# Geeky__Sheet1_copy_2023-02-18.net
KiCad netlist of a schematic drawn in Altium Designer
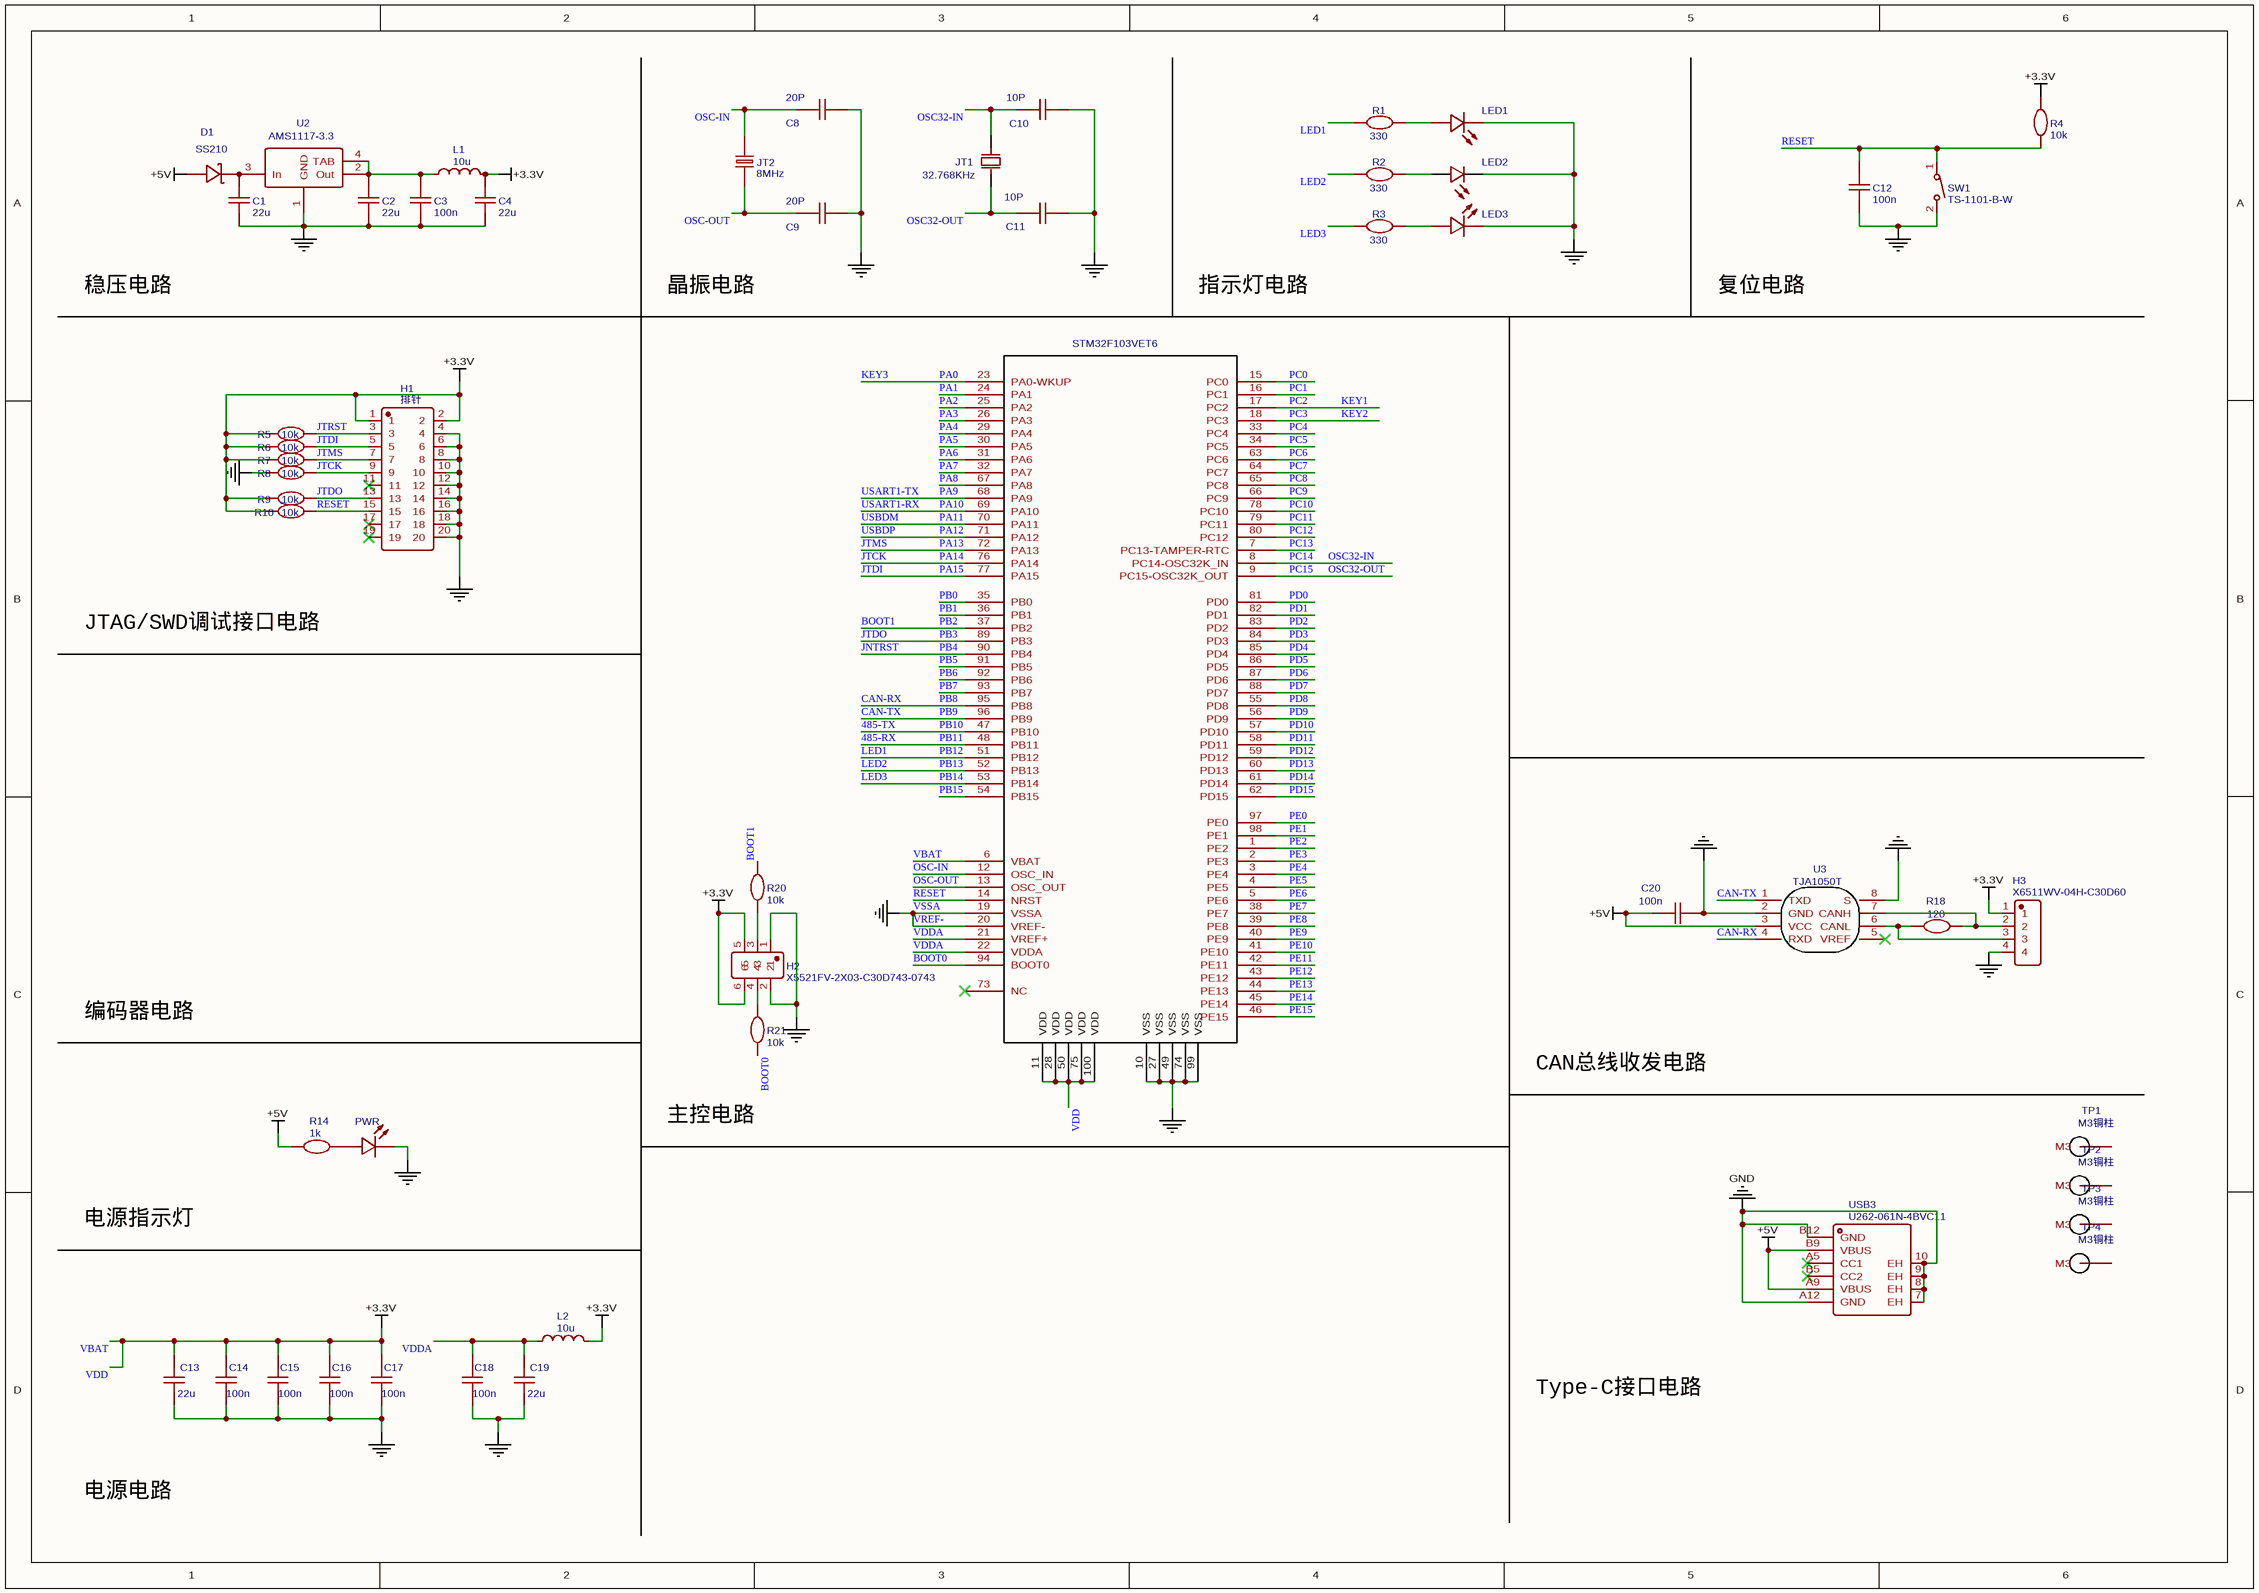
[diagram p0: _Geeky_ Sheet1 copy_2023-02-18.schdoc]

(export (version "E")
  (design (tool "Eeschema 10.0.6"))
  (components
    (comp (ref "C1") (value "22u") (footprint "0805") (libsource (lib "altium-import") (part "root_2_22u_")))
    (comp (ref "C2") (value "22u") (footprint "0805") (libsource (lib "altium-import") (part "root_2_22u_")))
    (comp (ref "C3")
      (value "100n")
      (footprint "0805")
      (libsource (lib "altium-import") (part "root_2_100n_"))
    )
    (comp (ref "C4") (value "22u") (footprint "0805") (libsource (lib "altium-import") (part "root_2_22u_")))
    (comp (ref "C8") (value "20P") (footprint "0805") (libsource (lib "altium-import") (part "root_1_20P_")))
    (comp (ref "C9") (value "20P") (footprint "0805") (libsource (lib "altium-import") (part "root_1_20P_")))
    (comp (ref "C10") (value "10P") (footprint "0805") (libsource (lib "altium-import") (part "root_1_10P_")))
    (comp (ref "C11") (value "10P") (footprint "0805") (libsource (lib "altium-import") (part "root_1_10P_")))
    (comp (ref "C12")
      (value "100n")
      (footprint "0805")
      (libsource (lib "altium-import") (part "root_2_100n_"))
    )
    (comp (ref "C13") (value "22u") (footprint "0805") (libsource (lib "altium-import") (part "root_0_22u_")))
    (comp (ref "C14")
      (value "100n")
      (footprint "0805")
      (libsource (lib "altium-import") (part "root_0_100n_"))
    )
    (comp (ref "C15")
      (value "100n")
      (footprint "0805")
      (libsource (lib "altium-import") (part "root_0_100n_"))
    )
    (comp (ref "C16")
      (value "100n")
      (footprint "0805")
      (libsource (lib "altium-import") (part "root_0_100n_"))
    )
    (comp (ref "C17")
      (value "100n")
      (footprint "0805")
      (libsource (lib "altium-import") (part "root_0_100n_"))
    )
    (comp (ref "C18")
      (value "100n")
      (footprint "0805")
      (libsource (lib "altium-import") (part "root_0_100n_"))
    )
    (comp (ref "C19") (value "22u") (footprint "0805") (libsource (lib "altium-import") (part "root_0_22u_")))
    (comp (ref "C20")
      (value "100n")
      (footprint "0805")
      (libsource (lib "altium-import") (part "root_3_100n_"))
    )
    (comp (ref "D1")
      (value "SS210")
      (footprint "SMA_L4.3-W2.6-LS5.2-FD")
      (fields (field (name "BOM_SUPPLIER PART") "C14996"))
      (libsource (lib "altium-import") (part "root_0_SS210_"))
    )
    (comp (ref "H1")
      (value "排针")
      (footprint "HDR-TH_20P-P2.54-V-M-R2-C10-S2.54-3")
      (fields
        (field (name "BOM_SUPPLIER PART") "C2764589")
        (field (name "BOM_MANUFACTURER PART") "X5521WV-2X10-C46D46-1220")
        (field (name "CONTRIBUTOR") "LCSC")
      )
      (libsource (lib "altium-import") (part "root_0_X5521WV-2X10-C46D46-1220_"))
    )
    (comp (ref "H2")
      (value "X5521FV-2X03-C30D743-0743")
      (footprint "HDR-TH_6P-P2.54-V-F-R2-C3-S2.54-3")
      (fields (field (name "BOM_SUPPLIER PART") "C2764576") (field (name "CONTRIBUTOR") "LCSC"))
      (libsource (lib "altium-import") (part "root_3_X5521FV-2X03-C30D743-0743_"))
    )
    (comp (ref "H3")
      (value "X6511WV-04H-C30D60")
      (footprint "HDR-TH_4P-P2.54-V-M")
      (fields (field (name "BOM_SUPPLIER PART") "C706876") (field (name "CONTRIBUTOR") "LCSC"))
      (libsource (lib "altium-import") (part "root_0_X6511WV-04H-C30D60_"))
    )
    (comp (ref "JT1")
      (value "32.768KHz")
      (footprint "OSC-SMD_L3.2-W1.5")
      (fields
        (field (name "BOM_MANUFACTURER PART") "NX3215SA 32.768KHZ 12.5PF 20PPM")
        (field (name "BOM_SUPPLIER PART") "C70509")
      )
      (libsource (lib "altium-import") (part "root_1_32.768KHz_"))
    )
    (comp (ref "JT2")
      (value "8MHz")
      (footprint "HC-49US_L11.5-W4.5-P4.88")
      (fields
        (field (name "BOM_SUPPLIER PART") "C295085")
        (field (name "BOM_MANUFACTURER PART") "XIHCELNANF-48MHZ")
        (field (name "CONTRIBUTOR") "LCSC")
      )
      (libsource (lib "altium-import") (part "root_1_8MHz_"))
    )
    (comp (ref "L1") (value "10u") (footprint "0805") (libsource (lib "altium-import") (part "root_0_10u_")))
    (comp (ref "L2") (value "10u") (footprint "0805") (libsource (lib "altium-import") (part "root_0_10u_")))
    (comp (ref "LED1")
      (value "17-21SUYC/TR8")
      (footprint "LED0805-RD")
      (fields (field (name "BOM_SUPPLIER PART") "C2296"))
      (libsource (lib "altium-import") (part "root_2_17-21SUYC/TR8_"))
    )
    (comp (ref "LED2")
      (value "17-21/BHC-XL2M2TY/3T")
      (footprint "LED0805-RD")
      (fields (field (name "BOM_SUPPLIER PART") "C72035"))
      (libsource (lib "altium-import") (part "root_2_17-21/BHC-XL2M2TY/3T_"))
    )
    (comp (ref "LED3")
      (value "D-W080508W1-KS2")
      (footprint "LED-0805")
      (fields (field (name "BOM_SUPPLIER PART") "C130115") (field (name "CONTRIBUTOR") "LCSC"))
      (libsource (lib "altium-import") (part "root_0_D-W080508W1-KS2_"))
    )
    (comp (ref "PWR")
      (value "17-21SURC/S530-A2/TR8")
      (footprint "LED-0805")
      (fields (field (name "BOM_SUPPLIER PART") "C131244") (field (name "CONTRIBUTOR") "LCSC"))
      (libsource (lib "altium-import") (part "root_0_17-21SURC/S530-A2/TR8_"))
    )
    (comp (ref "R1") (value "330") (footprint "0805") (libsource (lib "altium-import") (part "root_0_330_")))
    (comp (ref "R2") (value "330") (footprint "0805") (libsource (lib "altium-import") (part "root_0_330_")))
    (comp (ref "R3") (value "330") (footprint "0805") (libsource (lib "altium-import") (part "root_0_330_")))
    (comp (ref "R4") (value "10k") (footprint "0805") (libsource (lib "altium-import") (part "root_1_10k_")))
    (comp (ref "R5") (value "10k") (footprint "0805") (libsource (lib "altium-import") (part "root_2_10k_")))
    (comp (ref "R6") (value "10k") (footprint "0805") (libsource (lib "altium-import") (part "root_2_10k_")))
    (comp (ref "R7") (value "10k") (footprint "0805") (libsource (lib "altium-import") (part "root_2_10k_")))
    (comp (ref "R8") (value "10k") (footprint "0805") (libsource (lib "altium-import") (part "root_2_10k_")))
    (comp (ref "R9") (value "10k") (footprint "0805") (libsource (lib "altium-import") (part "root_2_10k_")))
    (comp (ref "R10") (value "10k") (footprint "0805") (libsource (lib "altium-import") (part "root_2_10k_")))
    (comp (ref "R14") (value "1k") (footprint "0805") (libsource (lib "altium-import") (part "root_0_1k_")))
    (comp (ref "R18") (value "120") (footprint "0805") (libsource (lib "altium-import") (part "root_0_120_")))
    (comp (ref "R20") (value "10k") (footprint "0805") (libsource (lib "altium-import") (part "root_1_10k_")))
    (comp (ref "R21") (value "10k") (footprint "0805") (libsource (lib "altium-import") (part "root_1_10k_")))
    (comp (ref "SW1")
      (value "TS-1101-B-W")
      (footprint "KEY-SMD_2P-L6.0-W3.6-P7.4-LS8.0-L")
      (fields (field (name "BOM_SUPPLIER PART") "C500065") (field (name "CONTRIBUTOR") "LCSC"))
      (libsource (lib "altium-import") (part "root_3_TS-1101-B-W_"))
    )
    (comp (ref "TP1")
      (value "M3铜柱")
      (footprint "M3铜柱_LCEDA")
      (fields (field (name "CONTRIBUTOR") "LGW123456"))
      (libsource (lib "altium-import") (part "root_0_M3铜柱_"))
    )
    (comp (ref "TP2")
      (value "M3铜柱")
      (footprint "M3铜柱_LCEDA")
      (fields (field (name "CONTRIBUTOR") "LGW123456"))
      (libsource (lib "altium-import") (part "root_0_M3铜柱_"))
    )
    (comp (ref "TP3")
      (value "M3铜柱")
      (footprint "M3铜柱_LCEDA")
      (fields (field (name "CONTRIBUTOR") "LGW123456"))
      (libsource (lib "altium-import") (part "root_0_M3铜柱_"))
    )
    (comp (ref "TP4")
      (value "M3铜柱")
      (footprint "M3铜柱_LCEDA")
      (fields (field (name "CONTRIBUTOR") "LGW123456"))
      (libsource (lib "altium-import") (part "root_0_M3铜柱_"))
    )
    (comp (ref "U1")
      (value "STM32F103VET6")
      (footprint "LQFP-100_L14.0-W14.0-P0.50-LS16.0-BL")
      (fields (field (name "BOM_SUPPLIER PART") "C8308"))
      (libsource (lib "altium-import") (part "root_0_STM32F103VET6_"))
    )
    (comp (ref "U2")
      (value "AMS1117-3.3")
      (footprint "SOT-223_L6.5-W3.5-P2.30-LS7.0-BR")
      (fields (field (name "BOM_SUPPLIER PART") "C165482") (field (name "CONTRIBUTOR") "LCSC"))
      (libsource (lib "altium-import") (part "root_0_AMS1117-3.3_"))
    )
    (comp (ref "U3")
      (value "TJA1050T")
      (footprint "SOIC-8_L5.0-W4.0-P1.27-LS6.0-BL")
      (fields
        (field (name "BOM_MANUFACTURER PART") "TJA1050T/CM,118")
        (field (name "BOM_SUPPLIER PART") "C6952")
      )
      (libsource (lib "altium-import") (part "root_0_TJA1050T_"))
    )
    (comp (ref "USB3")
      (value "U262-061N-4BVC11")
      (footprint "USB-SMD_U262-061N-4BVC11")
      (fields (field (name "BOM_SUPPLIER PART") "C2764612") (field (name "CONTRIBUTOR") "LCSC"))
      (libsource (lib "altium-import") (part "root_0_U262-061N-4BVC11_"))
    )
  )
  (nets
    (net (code "1") (name "+3.3V") (class "Default")
      (node (ref "C13") (pin "2") (pinfunction "2_2") (pintype "passive"))
      (node (ref "C14") (pin "2") (pinfunction "2_2") (pintype "passive"))
      (node (ref "C15") (pin "2") (pinfunction "2_2") (pintype "passive"))
      (node (ref "C16") (pin "2") (pinfunction "2_2") (pintype "passive"))
      (node (ref "C17") (pin "2") (pinfunction "2_2") (pintype "passive"))
      (node (ref "C4") (pin "1") (pinfunction "1_1") (pintype "passive"))
      (node (ref "H1") (pin "1") (pinfunction "1_1") (pintype "passive"))
      (node (ref "H1") (pin "2") (pinfunction "2_2") (pintype "passive"))
      (node (ref "H2") (pin "5") (pinfunction "5_5") (pintype "passive"))
      (node (ref "H2") (pin "6") (pinfunction "6_6") (pintype "passive"))
      (node (ref "H3") (pin "1") (pinfunction "1_1") (pintype "passive"))
      (node (ref "L1") (pin "2") (pinfunction "2_2") (pintype "passive"))
      (node (ref "L2") (pin "2") (pinfunction "2_2") (pintype "passive"))
      (node (ref "R10") (pin "2") (pinfunction "2_2") (pintype "passive"))
      (node (ref "R4") (pin "2") (pinfunction "2_2") (pintype "passive"))
      (node (ref "R5") (pin "2") (pinfunction "2_2") (pintype "passive"))
      (node (ref "R6") (pin "2") (pinfunction "2_2") (pintype "passive"))
      (node (ref "R7") (pin "2") (pinfunction "2_2") (pintype "passive"))
      (node (ref "R9") (pin "2") (pinfunction "2_2") (pintype "passive"))
      (node (ref "U1") (pin "100") (pinfunction "VDD_100") (pintype "passive"))
      (node (ref "U1") (pin "11") (pinfunction "VDD_11") (pintype "passive"))
      (node (ref "U1") (pin "28") (pinfunction "VDD_28") (pintype "passive"))
      (node (ref "U1") (pin "50") (pinfunction "VDD_50") (pintype "passive"))
      (node (ref "U1") (pin "6") (pinfunction "VBAT_6") (pintype "passive"))
      (node (ref "U1") (pin "75") (pinfunction "VDD_75") (pintype "passive"))
    )
    (net (code "2") (name "+5V") (class "Default")
      (node (ref "C20") (pin "1") (pinfunction "1_1") (pintype "passive"))
      (node (ref "D1") (pin "1") (pinfunction "A_1") (pintype "passive"))
      (node (ref "R14") (pin "1") (pinfunction "1_1") (pintype "passive"))
      (node (ref "U3") (pin "3") (pinfunction "VCC_3") (pintype "passive"))
      (node (ref "USB3") (pin "A9") (pinfunction "VBUS_A9") (pintype "passive"))
      (node (ref "USB3") (pin "B9") (pinfunction "VBUS_B9") (pintype "passive"))
    )
    (net (code "3") (name "/485-RX") (class "Default")
      (node (ref "U1") (pin "48") (pinfunction "PB11_48") (pintype "passive"))
    )
    (net (code "4") (name "/485-TX") (class "Default")
      (node (ref "U1") (pin "47") (pinfunction "PB10_47") (pintype "passive"))
    )
    (net (code "5") (name "/BOOT0") (class "Default")
      (node (ref "R21") (pin "1") (pinfunction "1_1") (pintype "passive"))
      (node (ref "U1") (pin "94") (pinfunction "BOOT0_94") (pintype "passive"))
    )
    (net (code "6") (name "/BOOT1") (class "Default")
      (node (ref "R20") (pin "2") (pinfunction "2_2") (pintype "passive"))
      (node (ref "U1") (pin "37") (pinfunction "PB2_37") (pintype "passive"))
    )
    (net (code "7") (name "/CAN-RX") (class "Default")
      (node (ref "U1") (pin "95") (pinfunction "PB8_95") (pintype "passive"))
      (node (ref "U3") (pin "4") (pinfunction "RXD_4") (pintype "passive"))
    )
    (net (code "8") (name "/CAN-TX") (class "Default")
      (node (ref "U1") (pin "96") (pinfunction "PB9_96") (pintype "passive"))
      (node (ref "U3") (pin "1") (pinfunction "TXD_1") (pintype "passive"))
    )
    (net (code "9") (name "/JNTRST") (class "Default")
      (node (ref "U1") (pin "90") (pinfunction "PB4_90") (pintype "passive"))
    )
    (net (code "10") (name "/JTCK") (class "Default")
      (node (ref "H1") (pin "9") (pinfunction "9_9") (pintype "passive"))
      (node (ref "R8") (pin "1") (pinfunction "1_1") (pintype "passive"))
      (node (ref "U1") (pin "76") (pinfunction "PA14_76") (pintype "passive"))
    )
    (net (code "11") (name "/JTDI") (class "Default")
      (node (ref "H1") (pin "5") (pinfunction "5_5") (pintype "passive"))
      (node (ref "R6") (pin "1") (pinfunction "1_1") (pintype "passive"))
      (node (ref "U1") (pin "77") (pinfunction "PA15_77") (pintype "passive"))
    )
    (net (code "12") (name "/JTDO") (class "Default")
      (node (ref "H1") (pin "13") (pinfunction "13_13") (pintype "passive"))
      (node (ref "R9") (pin "1") (pinfunction "1_1") (pintype "passive"))
      (node (ref "U1") (pin "89") (pinfunction "PB3_89") (pintype "passive"))
    )
    (net (code "13") (name "/JTMS") (class "Default")
      (node (ref "H1") (pin "7") (pinfunction "7_7") (pintype "passive"))
      (node (ref "R7") (pin "1") (pinfunction "1_1") (pintype "passive"))
      (node (ref "U1") (pin "72") (pinfunction "PA13_72") (pintype "passive"))
    )
    (net (code "14") (name "/JTRST") (class "Default")
      (node (ref "H1") (pin "3") (pinfunction "3_3") (pintype "passive"))
      (node (ref "R5") (pin "1") (pinfunction "1_1") (pintype "passive"))
    )
    (net (code "15") (name "/KEY1") (class "Default")
      (node (ref "U1") (pin "17") (pinfunction "PC2_17") (pintype "passive"))
    )
    (net (code "16") (name "/KEY2") (class "Default")
      (node (ref "U1") (pin "18") (pinfunction "PC3_18") (pintype "passive"))
    )
    (net (code "17") (name "/KEY3") (class "Default")
      (node (ref "U1") (pin "23") (pinfunction "PA0-WKUP_23") (pintype "passive"))
    )
    (net (code "18") (name "/LED1") (class "Default")
      (node (ref "R1") (pin "1") (pinfunction "1_1") (pintype "passive"))
      (node (ref "U1") (pin "51") (pinfunction "PB12_51") (pintype "passive"))
    )
    (net (code "19") (name "/LED2") (class "Default")
      (node (ref "R2") (pin "1") (pinfunction "1_1") (pintype "passive"))
      (node (ref "U1") (pin "52") (pinfunction "PB13_52") (pintype "passive"))
    )
    (net (code "20") (name "/LED3") (class "Default")
      (node (ref "R3") (pin "1") (pinfunction "1_1") (pintype "passive"))
      (node (ref "U1") (pin "53") (pinfunction "PB14_53") (pintype "passive"))
    )
    (net (code "21") (name "/OSC-IN") (class "Default")
      (node (ref "C8") (pin "2") (pinfunction "2_2") (pintype "passive"))
      (node (ref "JT2") (pin "2") (pinfunction "2_2") (pintype "passive"))
      (node (ref "U1") (pin "12") (pinfunction "OSC_IN_12") (pintype "passive"))
    )
    (net (code "22") (name "/OSC-OUT") (class "Default")
      (node (ref "C9") (pin "2") (pinfunction "2_2") (pintype "passive"))
      (node (ref "JT2") (pin "1") (pinfunction "1_1") (pintype "passive"))
      (node (ref "U1") (pin "13") (pinfunction "OSC_OUT_13") (pintype "passive"))
    )
    (net (code "23") (name "/OSC32-IN") (class "Default")
      (node (ref "C10") (pin "2") (pinfunction "2_2") (pintype "passive"))
      (node (ref "JT1") (pin "2") (pinfunction "OSC2_2") (pintype "passive"))
      (node (ref "U1") (pin "8") (pinfunction "PC14-OSC32K_IN_8") (pintype "passive"))
    )
    (net (code "24") (name "/OSC32-OUT") (class "Default")
      (node (ref "C11") (pin "2") (pinfunction "2_2") (pintype "passive"))
      (node (ref "JT1") (pin "1") (pinfunction "OSC1_1") (pintype "passive"))
      (node (ref "U1") (pin "9") (pinfunction "PC15-OSC32K_OUT_9") (pintype "passive"))
    )
    (net (code "25") (name "/PA1") (class "Default")
      (node (ref "U1") (pin "24") (pinfunction "PA1_24") (pintype "passive"))
    )
    (net (code "26") (name "/PA2") (class "Default")
      (node (ref "U1") (pin "25") (pinfunction "PA2_25") (pintype "passive"))
    )
    (net (code "27") (name "/PA3") (class "Default")
      (node (ref "U1") (pin "26") (pinfunction "PA3_26") (pintype "passive"))
    )
    (net (code "28") (name "/PA4") (class "Default")
      (node (ref "U1") (pin "29") (pinfunction "PA4_29") (pintype "passive"))
    )
    (net (code "29") (name "/PA5") (class "Default")
      (node (ref "U1") (pin "30") (pinfunction "PA5_30") (pintype "passive"))
    )
    (net (code "30") (name "/PA6") (class "Default")
      (node (ref "U1") (pin "31") (pinfunction "PA6_31") (pintype "passive"))
    )
    (net (code "31") (name "/PA7") (class "Default")
      (node (ref "U1") (pin "32") (pinfunction "PA7_32") (pintype "passive"))
    )
    (net (code "32") (name "/PA8") (class "Default")
      (node (ref "U1") (pin "67") (pinfunction "PA8_67") (pintype "passive"))
    )
    (net (code "33") (name "/PA9") (class "Default")
      (node (ref "U1") (pin "68") (pinfunction "PA9_68") (pintype "passive"))
    )
    (net (code "34") (name "/PA10") (class "Default")
      (node (ref "U1") (pin "69") (pinfunction "PA10_69") (pintype "passive"))
    )
    (net (code "35") (name "/PA11") (class "Default")
      (node (ref "U1") (pin "70") (pinfunction "PA11_70") (pintype "passive"))
    )
    (net (code "36") (name "/PA12") (class "Default")
      (node (ref "U1") (pin "71") (pinfunction "PA12_71") (pintype "passive"))
    )
    (net (code "37") (name "/PB0") (class "Default")
      (node (ref "U1") (pin "35") (pinfunction "PB0_35") (pintype "passive"))
    )
    (net (code "38") (name "/PB1") (class "Default")
      (node (ref "U1") (pin "36") (pinfunction "PB1_36") (pintype "passive"))
    )
    (net (code "39") (name "/PB5") (class "Default")
      (node (ref "U1") (pin "91") (pinfunction "PB5_91") (pintype "passive"))
    )
    (net (code "40") (name "/PB6") (class "Default")
      (node (ref "U1") (pin "92") (pinfunction "PB6_92") (pintype "passive"))
    )
    (net (code "41") (name "/PB7") (class "Default")
      (node (ref "U1") (pin "93") (pinfunction "PB7_93") (pintype "passive"))
    )
    (net (code "42") (name "/PB15") (class "Default")
      (node (ref "U1") (pin "54") (pinfunction "PB15_54") (pintype "passive"))
    )
    (net (code "43") (name "/PC0") (class "Default")
      (node (ref "U1") (pin "15") (pinfunction "PC0_15") (pintype "passive"))
    )
    (net (code "44") (name "/PC1") (class "Default")
      (node (ref "U1") (pin "16") (pinfunction "PC1_16") (pintype "passive"))
    )
    (net (code "45") (name "/PC4") (class "Default")
      (node (ref "U1") (pin "33") (pinfunction "PC4_33") (pintype "passive"))
    )
    (net (code "46") (name "/PC5") (class "Default")
      (node (ref "U1") (pin "34") (pinfunction "PC5_34") (pintype "passive"))
    )
    (net (code "47") (name "/PC6") (class "Default")
      (node (ref "U1") (pin "63") (pinfunction "PC6_63") (pintype "passive"))
    )
    (net (code "48") (name "/PC7") (class "Default")
      (node (ref "U1") (pin "64") (pinfunction "PC7_64") (pintype "passive"))
    )
    (net (code "49") (name "/PC8") (class "Default")
      (node (ref "U1") (pin "65") (pinfunction "PC8_65") (pintype "passive"))
    )
    (net (code "50") (name "/PC9") (class "Default")
      (node (ref "U1") (pin "66") (pinfunction "PC9_66") (pintype "passive"))
    )
    (net (code "51") (name "/PC10") (class "Default")
      (node (ref "U1") (pin "78") (pinfunction "PC10_78") (pintype "passive"))
    )
    (net (code "52") (name "/PC11") (class "Default")
      (node (ref "U1") (pin "79") (pinfunction "PC11_79") (pintype "passive"))
    )
    (net (code "53") (name "/PC12") (class "Default")
      (node (ref "U1") (pin "80") (pinfunction "PC12_80") (pintype "passive"))
    )
    (net (code "54") (name "/PC13") (class "Default")
      (node (ref "U1") (pin "7") (pinfunction "PC13-TAMPER-RTC_7") (pintype "passive"))
    )
    (net (code "55") (name "/PD0") (class "Default")
      (node (ref "U1") (pin "81") (pinfunction "PD0_81") (pintype "passive"))
    )
    (net (code "56") (name "/PD1") (class "Default")
      (node (ref "U1") (pin "82") (pinfunction "PD1_82") (pintype "passive"))
    )
    (net (code "57") (name "/PD2") (class "Default")
      (node (ref "U1") (pin "83") (pinfunction "PD2_83") (pintype "passive"))
    )
    (net (code "58") (name "/PD3") (class "Default")
      (node (ref "U1") (pin "84") (pinfunction "PD3_84") (pintype "passive"))
    )
    (net (code "59") (name "/PD4") (class "Default")
      (node (ref "U1") (pin "85") (pinfunction "PD4_85") (pintype "passive"))
    )
    (net (code "60") (name "/PD5") (class "Default")
      (node (ref "U1") (pin "86") (pinfunction "PD5_86") (pintype "passive"))
    )
    (net (code "61") (name "/PD6") (class "Default")
      (node (ref "U1") (pin "87") (pinfunction "PD6_87") (pintype "passive"))
    )
    (net (code "62") (name "/PD7") (class "Default")
      (node (ref "U1") (pin "88") (pinfunction "PD7_88") (pintype "passive"))
    )
    (net (code "63") (name "/PD8") (class "Default")
      (node (ref "U1") (pin "55") (pinfunction "PD8_55") (pintype "passive"))
    )
    (net (code "64") (name "/PD9") (class "Default")
      (node (ref "U1") (pin "56") (pinfunction "PD9_56") (pintype "passive"))
    )
    (net (code "65") (name "/PD10") (class "Default")
      (node (ref "U1") (pin "57") (pinfunction "PD10_57") (pintype "passive"))
    )
    (net (code "66") (name "/PD11") (class "Default")
      (node (ref "U1") (pin "58") (pinfunction "PD11_58") (pintype "passive"))
    )
    (net (code "67") (name "/PD12") (class "Default")
      (node (ref "U1") (pin "59") (pinfunction "PD12_59") (pintype "passive"))
    )
    (net (code "68") (name "/PD13") (class "Default")
      (node (ref "U1") (pin "60") (pinfunction "PD13_60") (pintype "passive"))
    )
    (net (code "69") (name "/PD14") (class "Default")
      (node (ref "U1") (pin "61") (pinfunction "PD14_61") (pintype "passive"))
    )
    (net (code "70") (name "/PD15") (class "Default")
      (node (ref "U1") (pin "62") (pinfunction "PD15_62") (pintype "passive"))
    )
    (net (code "71") (name "/PE0") (class "Default")
      (node (ref "U1") (pin "97") (pinfunction "PE0_97") (pintype "passive"))
    )
    (net (code "72") (name "/PE1") (class "Default")
      (node (ref "U1") (pin "98") (pinfunction "PE1_98") (pintype "passive"))
    )
    (net (code "73") (name "/PE2") (class "Default")
      (node (ref "U1") (pin "1") (pinfunction "PE2_1") (pintype "passive"))
    )
    (net (code "74") (name "/PE3") (class "Default")
      (node (ref "U1") (pin "2") (pinfunction "PE3_2") (pintype "passive"))
    )
    (net (code "75") (name "/PE4") (class "Default")
      (node (ref "U1") (pin "3") (pinfunction "PE4_3") (pintype "passive"))
    )
    (net (code "76") (name "/PE5") (class "Default")
      (node (ref "U1") (pin "4") (pinfunction "PE5_4") (pintype "passive"))
    )
    (net (code "77") (name "/PE6") (class "Default")
      (node (ref "U1") (pin "5") (pinfunction "PE6_5") (pintype "passive"))
    )
    (net (code "78") (name "/PE7") (class "Default")
      (node (ref "U1") (pin "38") (pinfunction "PE7_38") (pintype "passive"))
    )
    (net (code "79") (name "/PE8") (class "Default")
      (node (ref "U1") (pin "39") (pinfunction "PE8_39") (pintype "passive"))
    )
    (net (code "80") (name "/PE9") (class "Default")
      (node (ref "U1") (pin "40") (pinfunction "PE9_40") (pintype "passive"))
    )
    (net (code "81") (name "/PE10") (class "Default")
      (node (ref "U1") (pin "41") (pinfunction "PE10_41") (pintype "passive"))
    )
    (net (code "82") (name "/PE11") (class "Default")
      (node (ref "U1") (pin "42") (pinfunction "PE11_42") (pintype "passive"))
    )
    (net (code "83") (name "/PE12") (class "Default")
      (node (ref "U1") (pin "43") (pinfunction "PE12_43") (pintype "passive"))
    )
    (net (code "84") (name "/PE13") (class "Default")
      (node (ref "U1") (pin "44") (pinfunction "PE13_44") (pintype "passive"))
    )
    (net (code "85") (name "/PE14") (class "Default")
      (node (ref "U1") (pin "45") (pinfunction "PE14_45") (pintype "passive"))
    )
    (net (code "86") (name "/PE15") (class "Default")
      (node (ref "U1") (pin "46") (pinfunction "PE15_46") (pintype "passive"))
    )
    (net (code "87") (name "/RESET") (class "Default")
      (node (ref "C12") (pin "1") (pinfunction "1_1") (pintype "passive"))
      (node (ref "H1") (pin "15") (pinfunction "15_15") (pintype "passive"))
      (node (ref "R10") (pin "1") (pinfunction "1_1") (pintype "passive"))
      (node (ref "R4") (pin "1") (pinfunction "1_1") (pintype "passive"))
      (node (ref "SW1") (pin "1") (pinfunction "1_1") (pintype "passive"))
      (node (ref "U1") (pin "14") (pinfunction "NRST_14") (pintype "passive"))
    )
    (net (code "88") (name "/VDDA") (class "Default")
      (node (ref "C18") (pin "2") (pinfunction "2_2") (pintype "passive"))
      (node (ref "C19") (pin "2") (pinfunction "2_2") (pintype "passive"))
      (node (ref "L2") (pin "1") (pinfunction "1_1") (pintype "passive"))
      (node (ref "U1") (pin "21") (pinfunction "VREF+_21") (pintype "passive"))
      (node (ref "U1") (pin "22") (pinfunction "VDDA_22") (pintype "passive"))
    )
    (net (code "89") (name "GND") (class "Default")
      (node (ref "C1") (pin "2") (pinfunction "2_2") (pintype "passive"))
      (node (ref "C10") (pin "1") (pinfunction "1_1") (pintype "passive"))
      (node (ref "C11") (pin "1") (pinfunction "1_1") (pintype "passive"))
      (node (ref "C12") (pin "2") (pinfunction "2_2") (pintype "passive"))
      (node (ref "C13") (pin "1") (pinfunction "1_1") (pintype "passive"))
      (node (ref "C14") (pin "1") (pinfunction "1_1") (pintype "passive"))
      (node (ref "C15") (pin "1") (pinfunction "1_1") (pintype "passive"))
      (node (ref "C16") (pin "1") (pinfunction "1_1") (pintype "passive"))
      (node (ref "C17") (pin "1") (pinfunction "1_1") (pintype "passive"))
      (node (ref "C18") (pin "1") (pinfunction "1_1") (pintype "passive"))
      (node (ref "C19") (pin "1") (pinfunction "1_1") (pintype "passive"))
      (node (ref "C2") (pin "2") (pinfunction "2_2") (pintype "passive"))
      (node (ref "C20") (pin "2") (pinfunction "2_2") (pintype "passive"))
      (node (ref "C3") (pin "2") (pinfunction "2_2") (pintype "passive"))
      (node (ref "C4") (pin "2") (pinfunction "2_2") (pintype "passive"))
      (node (ref "C8") (pin "1") (pinfunction "1_1") (pintype "passive"))
      (node (ref "C9") (pin "1") (pinfunction "1_1") (pintype "passive"))
      (node (ref "H1") (pin "10") (pinfunction "10_10") (pintype "passive"))
      (node (ref "H1") (pin "12") (pinfunction "12_12") (pintype "passive"))
      (node (ref "H1") (pin "14") (pinfunction "14_14") (pintype "passive"))
      (node (ref "H1") (pin "16") (pinfunction "16_16") (pintype "passive"))
      (node (ref "H1") (pin "18") (pinfunction "18_18") (pintype "passive"))
      (node (ref "H1") (pin "20") (pinfunction "20_20") (pintype "passive"))
      (node (ref "H1") (pin "4") (pinfunction "4_4") (pintype "passive"))
      (node (ref "H1") (pin "6") (pinfunction "6_6") (pintype "passive"))
      (node (ref "H1") (pin "8") (pinfunction "8_8") (pintype "passive"))
      (node (ref "H2") (pin "1") (pinfunction "1_1") (pintype "passive"))
      (node (ref "H2") (pin "2") (pinfunction "2_2") (pintype "passive"))
      (node (ref "H3") (pin "4") (pinfunction "4_4") (pintype "passive"))
      (node (ref "LED1") (pin "1") (pinfunction "-_1") (pintype "passive"))
      (node (ref "LED2") (pin "1") (pinfunction "-_1") (pintype "passive"))
      (node (ref "LED3") (pin "2") (pinfunction "K_2") (pintype "passive"))
      (node (ref "PWR") (pin "2") (pinfunction "K_2") (pintype "passive"))
      (node (ref "R8") (pin "2") (pinfunction "2_2") (pintype "passive"))
      (node (ref "SW1") (pin "2") (pinfunction "2_2") (pintype "passive"))
      (node (ref "U1") (pin "10") (pinfunction "VSS_10") (pintype "passive"))
      (node (ref "U1") (pin "19") (pinfunction "VSSA_19") (pintype "passive"))
      (node (ref "U1") (pin "20") (pinfunction "VREF-_20") (pintype "passive"))
      (node (ref "U1") (pin "27") (pinfunction "VSS_27") (pintype "passive"))
      (node (ref "U1") (pin "49") (pinfunction "VSS_49") (pintype "passive"))
      (node (ref "U1") (pin "74") (pinfunction "VSS_74") (pintype "passive"))
      (node (ref "U1") (pin "99") (pinfunction "VSS_99") (pintype "passive"))
      (node (ref "U2") (pin "1") (pinfunction "GND_1") (pintype "passive"))
      (node (ref "U3") (pin "2") (pinfunction "GND_2") (pintype "passive"))
      (node (ref "U3") (pin "8") (pinfunction "S_8") (pintype "passive"))
      (node (ref "USB3") (pin "10") (pinfunction "EH_10") (pintype "passive"))
      (node (ref "USB3") (pin "7") (pinfunction "EH_7") (pintype "passive"))
      (node (ref "USB3") (pin "8") (pinfunction "EH_8") (pintype "passive"))
      (node (ref "USB3") (pin "9") (pinfunction "EH_9") (pintype "passive"))
      (node (ref "USB3") (pin "A12") (pinfunction "GND_A12") (pintype "passive"))
      (node (ref "USB3") (pin "B12") (pinfunction "GND_B12") (pintype "passive"))
    )
    (net (code "90") (name "Net-(D1-K)") (class "Default")
      (node (ref "C1") (pin "1") (pinfunction "1_1") (pintype "passive"))
      (node (ref "D1") (pin "2") (pinfunction "K_2") (pintype "passive"))
      (node (ref "U2") (pin "3") (pinfunction "In_3") (pintype "passive"))
    )
    (net (code "91") (name "Net-(H2-Pad3)") (class "Default")
      (node (ref "H2") (pin "3") (pinfunction "3_3") (pintype "passive"))
      (node (ref "R20") (pin "1") (pinfunction "1_1") (pintype "passive"))
    )
    (net (code "92") (name "Net-(H2-Pad4)") (class "Default")
      (node (ref "H2") (pin "4") (pinfunction "4_4") (pintype "passive"))
      (node (ref "R21") (pin "2") (pinfunction "2_2") (pintype "passive"))
    )
    (net (code "93") (name "Net-(LED1-+)") (class "Default")
      (node (ref "LED1") (pin "2") (pinfunction "+_2") (pintype "passive"))
      (node (ref "R1") (pin "2") (pinfunction "2_2") (pintype "passive"))
    )
    (net (code "94") (name "Net-(LED2-+)") (class "Default")
      (node (ref "LED2") (pin "2") (pinfunction "+_2") (pintype "passive"))
      (node (ref "R2") (pin "2") (pinfunction "2_2") (pintype "passive"))
    )
    (net (code "95") (name "Net-(LED3-A)") (class "Default")
      (node (ref "LED3") (pin "1") (pinfunction "A_1") (pintype "passive"))
      (node (ref "R3") (pin "2") (pinfunction "2_2") (pintype "passive"))
    )
    (net (code "96") (name "Net-(PWR-A)") (class "Default")
      (node (ref "PWR") (pin "1") (pinfunction "A_1") (pintype "passive"))
      (node (ref "R14") (pin "2") (pinfunction "2_2") (pintype "passive"))
    )
    (net (code "97") (name "Net-(U2-Out)") (class "Default")
      (node (ref "C2") (pin "1") (pinfunction "1_1") (pintype "passive"))
      (node (ref "C3") (pin "1") (pinfunction "1_1") (pintype "passive"))
      (node (ref "L1") (pin "1") (pinfunction "1_1") (pintype "passive"))
      (node (ref "U2") (pin "2") (pinfunction "Out_2") (pintype "passive"))
      (node (ref "U2") (pin "4") (pinfunction "TAB_4") (pintype "passive"))
    )
    (net (code "98") (name "Net-(U3-CANH)") (class "Default")
      (node (ref "H3") (pin "2") (pinfunction "2_2") (pintype "passive"))
      (node (ref "R18") (pin "2") (pinfunction "2_2") (pintype "passive"))
      (node (ref "U3") (pin "7") (pinfunction "CANH_7") (pintype "passive"))
    )
    (net (code "99") (name "Net-(U3-CANL)") (class "Default")
      (node (ref "H3") (pin "3") (pinfunction "3_3") (pintype "passive"))
      (node (ref "R18") (pin "1") (pinfunction "1_1") (pintype "passive"))
      (node (ref "U3") (pin "6") (pinfunction "CANL_6") (pintype "passive"))
    )
    (net (code "100") (name "unconnected-(H1-Pad11)") (class "Default")
      (node (ref "H1") (pin "11") (pinfunction "11_11") (pintype "passive+no_connect"))
    )
    (net (code "101") (name "unconnected-(H1-Pad17)") (class "Default")
      (node (ref "H1") (pin "17") (pinfunction "17_17") (pintype "passive+no_connect"))
    )
    (net (code "102") (name "unconnected-(H1-Pad19)") (class "Default")
      (node (ref "H1") (pin "19") (pinfunction "19_19") (pintype "passive+no_connect"))
    )
    (net (code "103") (name "unconnected-(TP1-M3-Pad1)") (class "Default")
      (node (ref "TP1") (pin "1") (pinfunction "M3_1") (pintype "passive"))
    )
    (net (code "104") (name "unconnected-(TP2-M3-Pad1)") (class "Default")
      (node (ref "TP2") (pin "1") (pinfunction "M3_1") (pintype "passive"))
    )
    (net (code "105") (name "unconnected-(TP3-M3-Pad1)") (class "Default")
      (node (ref "TP3") (pin "1") (pinfunction "M3_1") (pintype "passive"))
    )
    (net (code "106") (name "unconnected-(TP4-M3-Pad1)") (class "Default")
      (node (ref "TP4") (pin "1") (pinfunction "M3_1") (pintype "passive"))
    )
    (net (code "107") (name "unconnected-(U1-NC-Pad73)") (class "Default")
      (node (ref "U1") (pin "73") (pinfunction "NC_73") (pintype "passive+no_connect"))
    )
    (net (code "108") (name "unconnected-(U3-VREF-Pad5)") (class "Default")
      (node (ref "U3") (pin "5") (pinfunction "VREF_5") (pintype "passive+no_connect"))
    )
    (net (code "109") (name "unconnected-(USB3-CC1-PadA5)") (class "Default")
      (node (ref "USB3") (pin "A5") (pinfunction "CC1_A5") (pintype "passive+no_connect"))
    )
    (net (code "110") (name "unconnected-(USB3-CC2-PadB5)") (class "Default")
      (node (ref "USB3") (pin "B5") (pinfunction "CC2_B5") (pintype "passive+no_connect"))
    )
  )
)
